# fixed-SCH_Smart_Parking_IoT_2023-05-22.net
KiCad netlist of a schematic drawn in EasyEDA
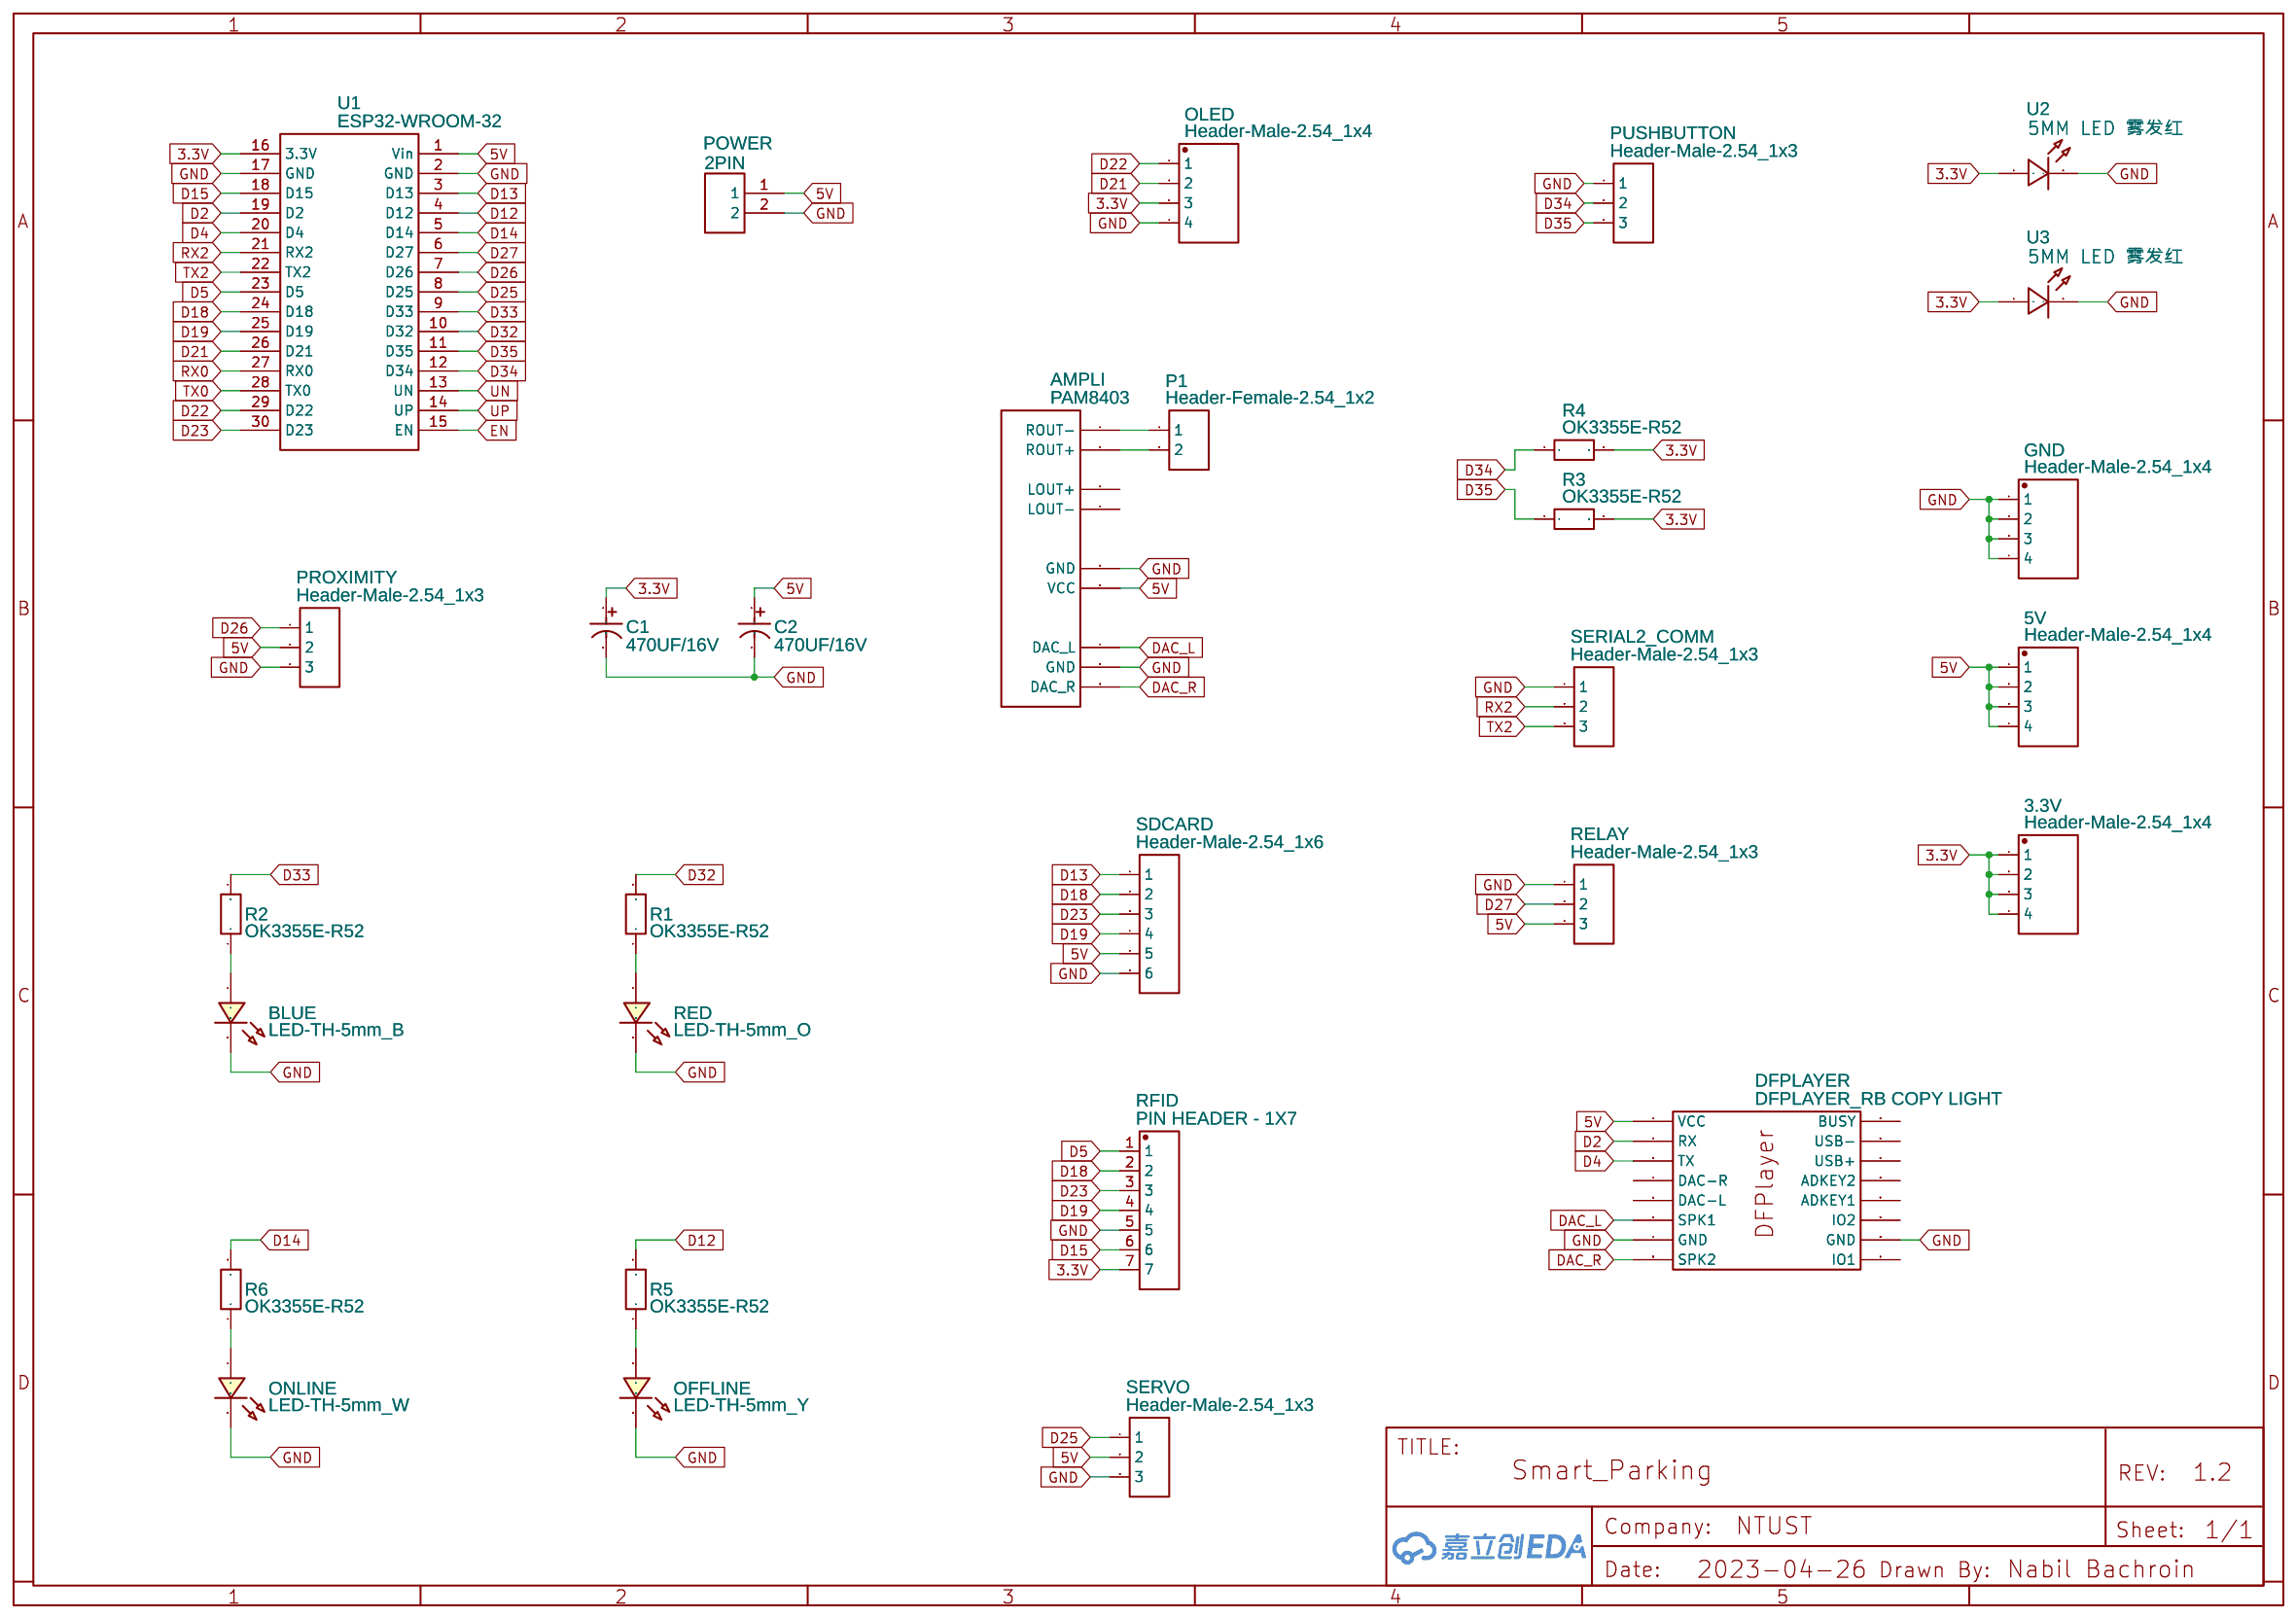
[diagram p0: schematic sheet]

(export (version "E")
  (design (tool "Eeschema 10.0.6"))
  (components
    (comp (ref "3.3V")
      (value "Header-Male-2.54_1x4")
      (fields
        (field (name "BOM_Manufacturer Part") "B-2100S04P-A110")
        (field (name "BOM_Supplier Part") "C124378")
      )
      (libsource (lib "") (part "Header-Male-2.54_1x4_1"))
    )
    (comp (ref "5V")
      (value "Header-Male-2.54_1x4")
      (fields
        (field (name "BOM_Manufacturer Part") "B-2100S04P-A110")
        (field (name "BOM_Supplier Part") "C124378")
      )
      (libsource (lib "") (part "Header-Male-2.54_1x4_2"))
    )
    (comp (ref "AMPLI") (value "PAM8403") (libsource (lib "") (part "PAM8403")))
    (comp (ref "BLUE") (value "LED-TH-5mm_B") (libsource (lib "") (part "LED-TH-5mm_B")))
    (comp (ref "C1")
      (value "470UF/16V")
      (fields
        (field (name "BOM_Manufacturer Part") "470uF/16V")
        (field (name "BOM_Supplier Part") "C9900008131")
      )
      (libsource (lib "") (part "470UF/16V"))
    )
    (comp (ref "C2")
      (value "470UF/16V")
      (fields
        (field (name "BOM_Manufacturer Part") "470uF/16V")
        (field (name "BOM_Supplier Part") "C9900008131")
      )
      (libsource (lib "") (part "470UF/16V"))
    )
    (comp (ref "DFPLAYER")
      (value "DFPLAYER_RB COPY LIGHT")
      (fields (field (name "BOM_Manufacturer Part") "DFPLAYER"))
      (libsource (lib "") (part "DFPLAYER_RB COPY LIGHT"))
    )
    (comp (ref "GND")
      (value "Header-Male-2.54_1x4")
      (fields
        (field (name "BOM_Manufacturer Part") "B-2100S04P-A110")
        (field (name "BOM_Supplier Part") "C124378")
      )
      (libsource (lib "") (part "Header-Male-2.54_1x4"))
    )
    (comp (ref "OFFLINE") (value "LED-TH-5mm_Y") (libsource (lib "") (part "LED-TH-5mm_Y")))
    (comp (ref "OLED")
      (value "Header-Male-2.54_1x4")
      (fields
        (field (name "BOM_Manufacturer Part") "B-2100S04P-A110")
        (field (name "BOM_Supplier Part") "C124378")
      )
      (libsource (lib "") (part "Header-Male-2.54_1x4_3"))
    )
    (comp (ref "ONLINE") (value "LED-TH-5mm_W") (libsource (lib "") (part "LED-TH-5mm_W")))
    (comp (ref "P1")
      (value "Header-Female-2.54_1x2")
      (fields (field (name "BOM_Manufacturer Part") "2.54-1*2P母") (field (name "BOM_Supplier Part") "C49661"))
      (libsource (lib "") (part "Header-Female-2.54_1x2"))
    )
    (comp (ref "POWER")
      (value "2PIN")
      (fields (field (name "BOM_Manufacturer Part") "Pin_Header_2"))
      (libsource (lib "") (part "2PIN"))
    )
    (comp (ref "PROXIMITY")
      (value "Header-Male-2.54_1x3")
      (fields (field (name "BOM_Manufacturer Part") "2.54-1*3P针") (field (name "BOM_Supplier Part") "C49257"))
      (libsource (lib "") (part "Header-Male-2.54_1x3"))
    )
    (comp (ref "PUSHBUTTON")
      (value "Header-Male-2.54_1x3")
      (fields (field (name "BOM_Manufacturer Part") "2.54-1*3P针") (field (name "BOM_Supplier Part") "C49257"))
      (libsource (lib "") (part "Header-Male-2.54_1x3_2"))
    )
    (comp (ref "R1")
      (value "OK3355E-R52")
      (fields (field (name "BOM_Supplier Part") "C3522642"))
      (libsource (lib "") (part "OK3355E-R52"))
    )
    (comp (ref "R2")
      (value "OK3355E-R52")
      (fields (field (name "BOM_Supplier Part") "C3522642"))
      (libsource (lib "") (part "OK3355E-R52"))
    )
    (comp (ref "R3")
      (value "OK3355E-R52")
      (fields (field (name "BOM_Supplier Part") "C3522642"))
      (libsource (lib "") (part "OK3355E-R52_1"))
    )
    (comp (ref "R4")
      (value "OK3355E-R52")
      (fields (field (name "BOM_Supplier Part") "C3522642"))
      (libsource (lib "") (part "OK3355E-R52_1"))
    )
    (comp (ref "R5")
      (value "OK3355E-R52")
      (fields (field (name "BOM_Supplier Part") "C3522642"))
      (libsource (lib "") (part "OK3355E-R52"))
    )
    (comp (ref "R6")
      (value "OK3355E-R52")
      (fields (field (name "BOM_Supplier Part") "C3522642"))
      (libsource (lib "") (part "OK3355E-R52"))
    )
    (comp (ref "RED") (value "LED-TH-5mm_O") (libsource (lib "") (part "LED-TH-5mm_O")))
    (comp (ref "RELAY")
      (value "Header-Male-2.54_1x3")
      (fields (field (name "BOM_Manufacturer Part") "2.54-1*3P针") (field (name "BOM_Supplier Part") "C49257"))
      (libsource (lib "") (part "Header-Male-2.54_1x3_4"))
    )
    (comp (ref "RFID") (value "PIN HEADER - 1X7") (libsource (lib "") (part "PIN HEADER - 1X7")))
    (comp (ref "SDCARD")
      (value "Header-Male-2.54_1x6")
      (fields
        (field (name "BOM_Manufacturer Part") "2.54-1x6P直针")
        (field (name "BOM_Supplier Part") "C37208")
      )
      (libsource (lib "") (part "Header-Male-2.54_1x6"))
    )
    (comp (ref "SERIAL2_COMM")
      (value "Header-Male-2.54_1x3")
      (fields (field (name "BOM_Manufacturer Part") "2.54-1*3P针") (field (name "BOM_Supplier Part") "C49257"))
      (libsource (lib "") (part "Header-Male-2.54_1x3_1"))
    )
    (comp (ref "SERVO")
      (value "Header-Male-2.54_1x3")
      (fields (field (name "BOM_Manufacturer Part") "2.54-1*3P针") (field (name "BOM_Supplier Part") "C49257"))
      (libsource (lib "") (part "Header-Male-2.54_1x3_3"))
    )
    (comp (ref "U1") (value "ESP32-WROOM-32") (libsource (lib "") (part "ESP32-WROOM-32")))
    (comp (ref "U2")
      (value "5MM LED 雾发红")
      (fields
        (field (name "BOM_Manufacturer Part") "5mm LED 雾发红")
        (field (name "BOM_Supplier Part") "C9900034380")
      )
      (libsource (lib "") (part "5MM LED 雾发红"))
    )
    (comp (ref "U3")
      (value "5MM LED 雾发红")
      (fields
        (field (name "BOM_Manufacturer Part") "5mm LED 雾发红")
        (field (name "BOM_Supplier Part") "C9900034380")
      )
      (libsource (lib "") (part "5MM LED 雾发红"))
    )
  )
  (nets
    (net (code "1") (name "3.3V") (class "Default")
      (node (ref "3.3V") (pin "1") (pinfunction "1_1") (pintype "unspecified"))
      (node (ref "3.3V") (pin "2") (pinfunction "2_2") (pintype "unspecified"))
      (node (ref "3.3V") (pin "3") (pinfunction "3_3") (pintype "unspecified"))
      (node (ref "3.3V") (pin "4") (pinfunction "4_4") (pintype "unspecified"))
      (node (ref "C1") (pin "1") (pinfunction "1_1") (pintype "input"))
      (node (ref "OLED") (pin "3") (pinfunction "3_3") (pintype "unspecified"))
      (node (ref "R3") (pin "2") (pinfunction "2_2") (pintype "unspecified"))
      (node (ref "R4") (pin "2") (pinfunction "2_2") (pintype "unspecified"))
      (node (ref "RFID") (pin "7") (pinfunction "7_7") (pintype "unspecified"))
      (node (ref "U1") (pin "16") (pinfunction "3.3V_16") (pintype "unspecified"))
      (node (ref "U2") (pin "1") (pinfunction "+_1") (pintype "unspecified"))
      (node (ref "U3") (pin "1") (pinfunction "+_1") (pintype "unspecified"))
    )
    (net (code "2") (name "5V") (class "Default")
      (node (ref "5V") (pin "1") (pinfunction "1_1") (pintype "unspecified"))
      (node (ref "5V") (pin "2") (pinfunction "2_2") (pintype "unspecified"))
      (node (ref "5V") (pin "3") (pinfunction "3_3") (pintype "unspecified"))
      (node (ref "5V") (pin "4") (pinfunction "4_4") (pintype "unspecified"))
      (node (ref "AMPLI") (pin "6") (pinfunction "VCC_6") (pintype "unspecified"))
      (node (ref "C2") (pin "1") (pinfunction "1_1") (pintype "input"))
      (node (ref "DFPLAYER") (pin "1") (pinfunction "VCC_1") (pintype "unspecified"))
      (node (ref "POWER") (pin "1") (pinfunction "1_1") (pintype "unspecified"))
      (node (ref "PROXIMITY") (pin "2") (pinfunction "2_2") (pintype "input"))
      (node (ref "RELAY") (pin "3") (pinfunction "3_3") (pintype "input"))
      (node (ref "SDCARD") (pin "5") (pinfunction "5_5") (pintype "input"))
      (node (ref "SERVO") (pin "2") (pinfunction "2_2") (pintype "input"))
      (node (ref "U1") (pin "1") (pinfunction "Vin_1") (pintype "unspecified"))
    )
    (net (code "3") (name "D2") (class "Default")
      (node (ref "DFPLAYER") (pin "2") (pinfunction "RX_2") (pintype "unspecified"))
      (node (ref "U1") (pin "19") (pinfunction "D2_19") (pintype "unspecified"))
    )
    (net (code "4") (name "D4") (class "Default")
      (node (ref "DFPLAYER") (pin "3") (pinfunction "TX_3") (pintype "unspecified"))
      (node (ref "U1") (pin "20") (pinfunction "D4_20") (pintype "unspecified"))
    )
    (net (code "5") (name "D5") (class "Default")
      (node (ref "RFID") (pin "1") (pinfunction "1_1") (pintype "unspecified"))
      (node (ref "U1") (pin "23") (pinfunction "D5_23") (pintype "unspecified"))
    )
    (net (code "6") (name "D12") (class "Default")
      (node (ref "R5") (pin "2") (pinfunction "2_2") (pintype "unspecified"))
      (node (ref "U1") (pin "4") (pinfunction "D12_4") (pintype "unspecified"))
    )
    (net (code "7") (name "D13") (class "Default")
      (node (ref "SDCARD") (pin "1") (pinfunction "1_1") (pintype "input"))
      (node (ref "U1") (pin "3") (pinfunction "D13_3") (pintype "unspecified"))
    )
    (net (code "8") (name "D14") (class "Default")
      (node (ref "R6") (pin "2") (pinfunction "2_2") (pintype "unspecified"))
      (node (ref "U1") (pin "5") (pinfunction "D14_5") (pintype "unspecified"))
    )
    (net (code "9") (name "D15") (class "Default")
      (node (ref "RFID") (pin "6") (pinfunction "6_6") (pintype "unspecified"))
      (node (ref "U1") (pin "18") (pinfunction "D15_18") (pintype "unspecified"))
    )
    (net (code "10") (name "D18") (class "Default")
      (node (ref "RFID") (pin "2") (pinfunction "2_2") (pintype "unspecified"))
      (node (ref "SDCARD") (pin "2") (pinfunction "2_2") (pintype "input"))
      (node (ref "U1") (pin "24") (pinfunction "D18_24") (pintype "unspecified"))
    )
    (net (code "11") (name "D19") (class "Default")
      (node (ref "RFID") (pin "4") (pinfunction "4_4") (pintype "unspecified"))
      (node (ref "SDCARD") (pin "4") (pinfunction "4_4") (pintype "input"))
      (node (ref "U1") (pin "25") (pinfunction "D19_25") (pintype "unspecified"))
    )
    (net (code "12") (name "D21") (class "Default")
      (node (ref "OLED") (pin "2") (pinfunction "2_2") (pintype "unspecified"))
      (node (ref "U1") (pin "26") (pinfunction "D21_26") (pintype "unspecified"))
    )
    (net (code "13") (name "D22") (class "Default")
      (node (ref "OLED") (pin "1") (pinfunction "1_1") (pintype "unspecified"))
      (node (ref "U1") (pin "29") (pinfunction "D22_29") (pintype "unspecified"))
    )
    (net (code "14") (name "D23") (class "Default")
      (node (ref "RFID") (pin "3") (pinfunction "3_3") (pintype "unspecified"))
      (node (ref "SDCARD") (pin "3") (pinfunction "3_3") (pintype "input"))
      (node (ref "U1") (pin "30") (pinfunction "D23_30") (pintype "unspecified"))
    )
    (net (code "15") (name "D25") (class "Default")
      (node (ref "SERVO") (pin "1") (pinfunction "1_1") (pintype "input"))
      (node (ref "U1") (pin "8") (pinfunction "D25_8") (pintype "unspecified"))
    )
    (net (code "16") (name "D26") (class "Default")
      (node (ref "PROXIMITY") (pin "1") (pinfunction "1_1") (pintype "input"))
      (node (ref "U1") (pin "7") (pinfunction "D26_7") (pintype "unspecified"))
    )
    (net (code "17") (name "D27") (class "Default")
      (node (ref "RELAY") (pin "2") (pinfunction "2_2") (pintype "input"))
      (node (ref "U1") (pin "6") (pinfunction "D27_6") (pintype "unspecified"))
    )
    (net (code "18") (name "D32") (class "Default")
      (node (ref "R1") (pin "2") (pinfunction "2_2") (pintype "unspecified"))
      (node (ref "U1") (pin "10") (pinfunction "D32_10") (pintype "unspecified"))
    )
    (net (code "19") (name "D33") (class "Default")
      (node (ref "R2") (pin "2") (pinfunction "2_2") (pintype "unspecified"))
      (node (ref "U1") (pin "9") (pinfunction "D33_9") (pintype "unspecified"))
    )
    (net (code "20") (name "D34") (class "Default")
      (node (ref "PUSHBUTTON") (pin "2") (pinfunction "2_2") (pintype "input"))
      (node (ref "R4") (pin "1") (pinfunction "1_1") (pintype "unspecified"))
      (node (ref "U1") (pin "12") (pinfunction "D34_12") (pintype "unspecified"))
    )
    (net (code "21") (name "D35") (class "Default")
      (node (ref "PUSHBUTTON") (pin "3") (pinfunction "3_3") (pintype "input"))
      (node (ref "R3") (pin "1") (pinfunction "1_1") (pintype "unspecified"))
      (node (ref "U1") (pin "11") (pinfunction "D35_11") (pintype "unspecified"))
    )
    (net (code "22") (name "DAC_L") (class "Default")
      (node (ref "AMPLI") (pin "7") (pinfunction "DAC_L_7") (pintype "unspecified"))
      (node (ref "DFPLAYER") (pin "6") (pinfunction "SPK1_6") (pintype "unspecified"))
    )
    (net (code "23") (name "DAC_R") (class "Default")
      (node (ref "AMPLI") (pin "9") (pinfunction "DAC_R_9") (pintype "unspecified"))
      (node (ref "DFPLAYER") (pin "8") (pinfunction "SPK2_8") (pintype "unspecified"))
    )
    (net (code "24") (name "EN") (class "Default")
      (node (ref "U1") (pin "15") (pinfunction "EN_15") (pintype "unspecified"))
    )
    (net (code "25") (name "GND") (class "Default")
      (node (ref "AMPLI") (pin "5") (pinfunction "GND_5") (pintype "unspecified"))
      (node (ref "AMPLI") (pin "8") (pinfunction "GND_8") (pintype "unspecified"))
      (node (ref "BLUE") (pin "2") (pinfunction "2_2") (pintype "unspecified"))
      (node (ref "C1") (pin "2") (pinfunction "2_2") (pintype "input"))
      (node (ref "C2") (pin "2") (pinfunction "2_2") (pintype "input"))
      (node (ref "DFPLAYER") (pin "10") (pinfunction "GND_10") (pintype "unspecified"))
      (node (ref "DFPLAYER") (pin "7") (pinfunction "GND_7") (pintype "unspecified"))
      (node (ref "GND") (pin "1") (pinfunction "1_1") (pintype "unspecified"))
      (node (ref "GND") (pin "2") (pinfunction "2_2") (pintype "unspecified"))
      (node (ref "GND") (pin "3") (pinfunction "3_3") (pintype "unspecified"))
      (node (ref "GND") (pin "4") (pinfunction "4_4") (pintype "unspecified"))
      (node (ref "OFFLINE") (pin "2") (pinfunction "2_2") (pintype "unspecified"))
      (node (ref "OLED") (pin "4") (pinfunction "4_4") (pintype "unspecified"))
      (node (ref "ONLINE") (pin "2") (pinfunction "2_2") (pintype "unspecified"))
      (node (ref "POWER") (pin "2") (pinfunction "2_2") (pintype "unspecified"))
      (node (ref "PROXIMITY") (pin "3") (pinfunction "3_3") (pintype "input"))
      (node (ref "PUSHBUTTON") (pin "1") (pinfunction "1_1") (pintype "input"))
      (node (ref "RED") (pin "2") (pinfunction "2_2") (pintype "unspecified"))
      (node (ref "RELAY") (pin "1") (pinfunction "1_1") (pintype "input"))
      (node (ref "RFID") (pin "5") (pinfunction "5_5") (pintype "unspecified"))
      (node (ref "SDCARD") (pin "6") (pinfunction "6_6") (pintype "input"))
      (node (ref "SERIAL2_COMM") (pin "1") (pinfunction "1_1") (pintype "input"))
      (node (ref "SERVO") (pin "3") (pinfunction "3_3") (pintype "input"))
      (node (ref "U1") (pin "17") (pinfunction "GND_17") (pintype "unspecified"))
      (node (ref "U1") (pin "2") (pinfunction "GND_2") (pintype "unspecified"))
      (node (ref "U2") (pin "2") (pinfunction "-_2") (pintype "unspecified"))
      (node (ref "U3") (pin "2") (pinfunction "-_2") (pintype "unspecified"))
    )
    (net (code "26") (name "Net-(AMPLI-ROUT+)") (class "Default")
      (node (ref "AMPLI") (pin "2") (pinfunction "ROUT+_2") (pintype "unspecified"))
      (node (ref "P1") (pin "2") (pinfunction "2_2") (pintype "input"))
    )
    (net (code "27") (name "Net-(AMPLI-ROUT-)") (class "Default")
      (node (ref "AMPLI") (pin "1") (pinfunction "ROUT-_1") (pintype "unspecified"))
      (node (ref "P1") (pin "1") (pinfunction "1_1") (pintype "input"))
    )
    (net (code "28") (name "Net-(BLUE-Pad1)") (class "Default")
      (node (ref "BLUE") (pin "1") (pinfunction "1_1") (pintype "unspecified"))
      (node (ref "R2") (pin "1") (pinfunction "1_1") (pintype "unspecified"))
    )
    (net (code "29") (name "Net-(OFFLINE-Pad1)") (class "Default")
      (node (ref "OFFLINE") (pin "1") (pinfunction "1_1") (pintype "unspecified"))
      (node (ref "R5") (pin "1") (pinfunction "1_1") (pintype "unspecified"))
    )
    (net (code "30") (name "Net-(ONLINE-Pad1)") (class "Default")
      (node (ref "ONLINE") (pin "1") (pinfunction "1_1") (pintype "unspecified"))
      (node (ref "R6") (pin "1") (pinfunction "1_1") (pintype "unspecified"))
    )
    (net (code "31") (name "Net-(R1-Pad1)") (class "Default")
      (node (ref "R1") (pin "1") (pinfunction "1_1") (pintype "unspecified"))
      (node (ref "RED") (pin "1") (pinfunction "1_1") (pintype "unspecified"))
    )
    (net (code "32") (name "RX0") (class "Default")
      (node (ref "U1") (pin "27") (pinfunction "RX0_27") (pintype "unspecified"))
    )
    (net (code "33") (name "RX2") (class "Default")
      (node (ref "SERIAL2_COMM") (pin "2") (pinfunction "2_2") (pintype "input"))
      (node (ref "U1") (pin "21") (pinfunction "RX2_21") (pintype "unspecified"))
    )
    (net (code "34") (name "TX0") (class "Default")
      (node (ref "U1") (pin "28") (pinfunction "TX0_28") (pintype "unspecified"))
    )
    (net (code "35") (name "TX2") (class "Default")
      (node (ref "SERIAL2_COMM") (pin "3") (pinfunction "3_3") (pintype "input"))
      (node (ref "U1") (pin "22") (pinfunction "TX2_22") (pintype "unspecified"))
    )
    (net (code "36") (name "UN") (class "Default")
      (node (ref "U1") (pin "13") (pinfunction "UN_13") (pintype "unspecified"))
    )
    (net (code "37") (name "UP") (class "Default")
      (node (ref "U1") (pin "14") (pinfunction "UP_14") (pintype "unspecified"))
    )
    (net (code "38") (name "unconnected-(AMPLI-LOUT+-Pad3)") (class "Default")
      (node (ref "AMPLI") (pin "3") (pinfunction "LOUT+_3") (pintype "unspecified"))
    )
    (net (code "39") (name "unconnected-(AMPLI-LOUT--Pad4)") (class "Default")
      (node (ref "AMPLI") (pin "4") (pinfunction "LOUT-_4") (pintype "unspecified"))
    )
    (net (code "40") (name "unconnected-(DFPLAYER-ADKEY1-Pad12)") (class "Default")
      (node (ref "DFPLAYER") (pin "12") (pinfunction "ADKEY1_12") (pintype "unspecified"))
    )
    (net (code "41") (name "unconnected-(DFPLAYER-ADKEY2-Pad13)") (class "Default")
      (node (ref "DFPLAYER") (pin "13") (pinfunction "ADKEY2_13") (pintype "unspecified"))
    )
    (net (code "42") (name "unconnected-(DFPLAYER-BUSY-Pad16)") (class "Default")
      (node (ref "DFPLAYER") (pin "16") (pinfunction "BUSY_16") (pintype "unspecified"))
    )
    (net (code "43") (name "unconnected-(DFPLAYER-DAC-L-Pad5)") (class "Default")
      (node (ref "DFPLAYER") (pin "5") (pinfunction "DAC-L_5") (pintype "unspecified"))
    )
    (net (code "44") (name "unconnected-(DFPLAYER-DAC-R-Pad4)") (class "Default")
      (node (ref "DFPLAYER") (pin "4") (pinfunction "DAC-R_4") (pintype "unspecified"))
    )
    (net (code "45") (name "unconnected-(DFPLAYER-IO1-Pad9)") (class "Default")
      (node (ref "DFPLAYER") (pin "9") (pinfunction "IO1_9") (pintype "unspecified"))
    )
    (net (code "46") (name "unconnected-(DFPLAYER-IO2-Pad11)") (class "Default")
      (node (ref "DFPLAYER") (pin "11") (pinfunction "IO2_11") (pintype "unspecified"))
    )
    (net (code "47") (name "unconnected-(DFPLAYER-USB+-Pad14)") (class "Default")
      (node (ref "DFPLAYER") (pin "14") (pinfunction "USB+_14") (pintype "unspecified"))
    )
    (net (code "48") (name "unconnected-(DFPLAYER-USB--Pad15)") (class "Default")
      (node (ref "DFPLAYER") (pin "15") (pinfunction "USB-_15") (pintype "unspecified"))
    )
  )
)
